# MIXR_Power_-_Connectors.net
KiCad netlist of a schematic drawn in Altium Designer
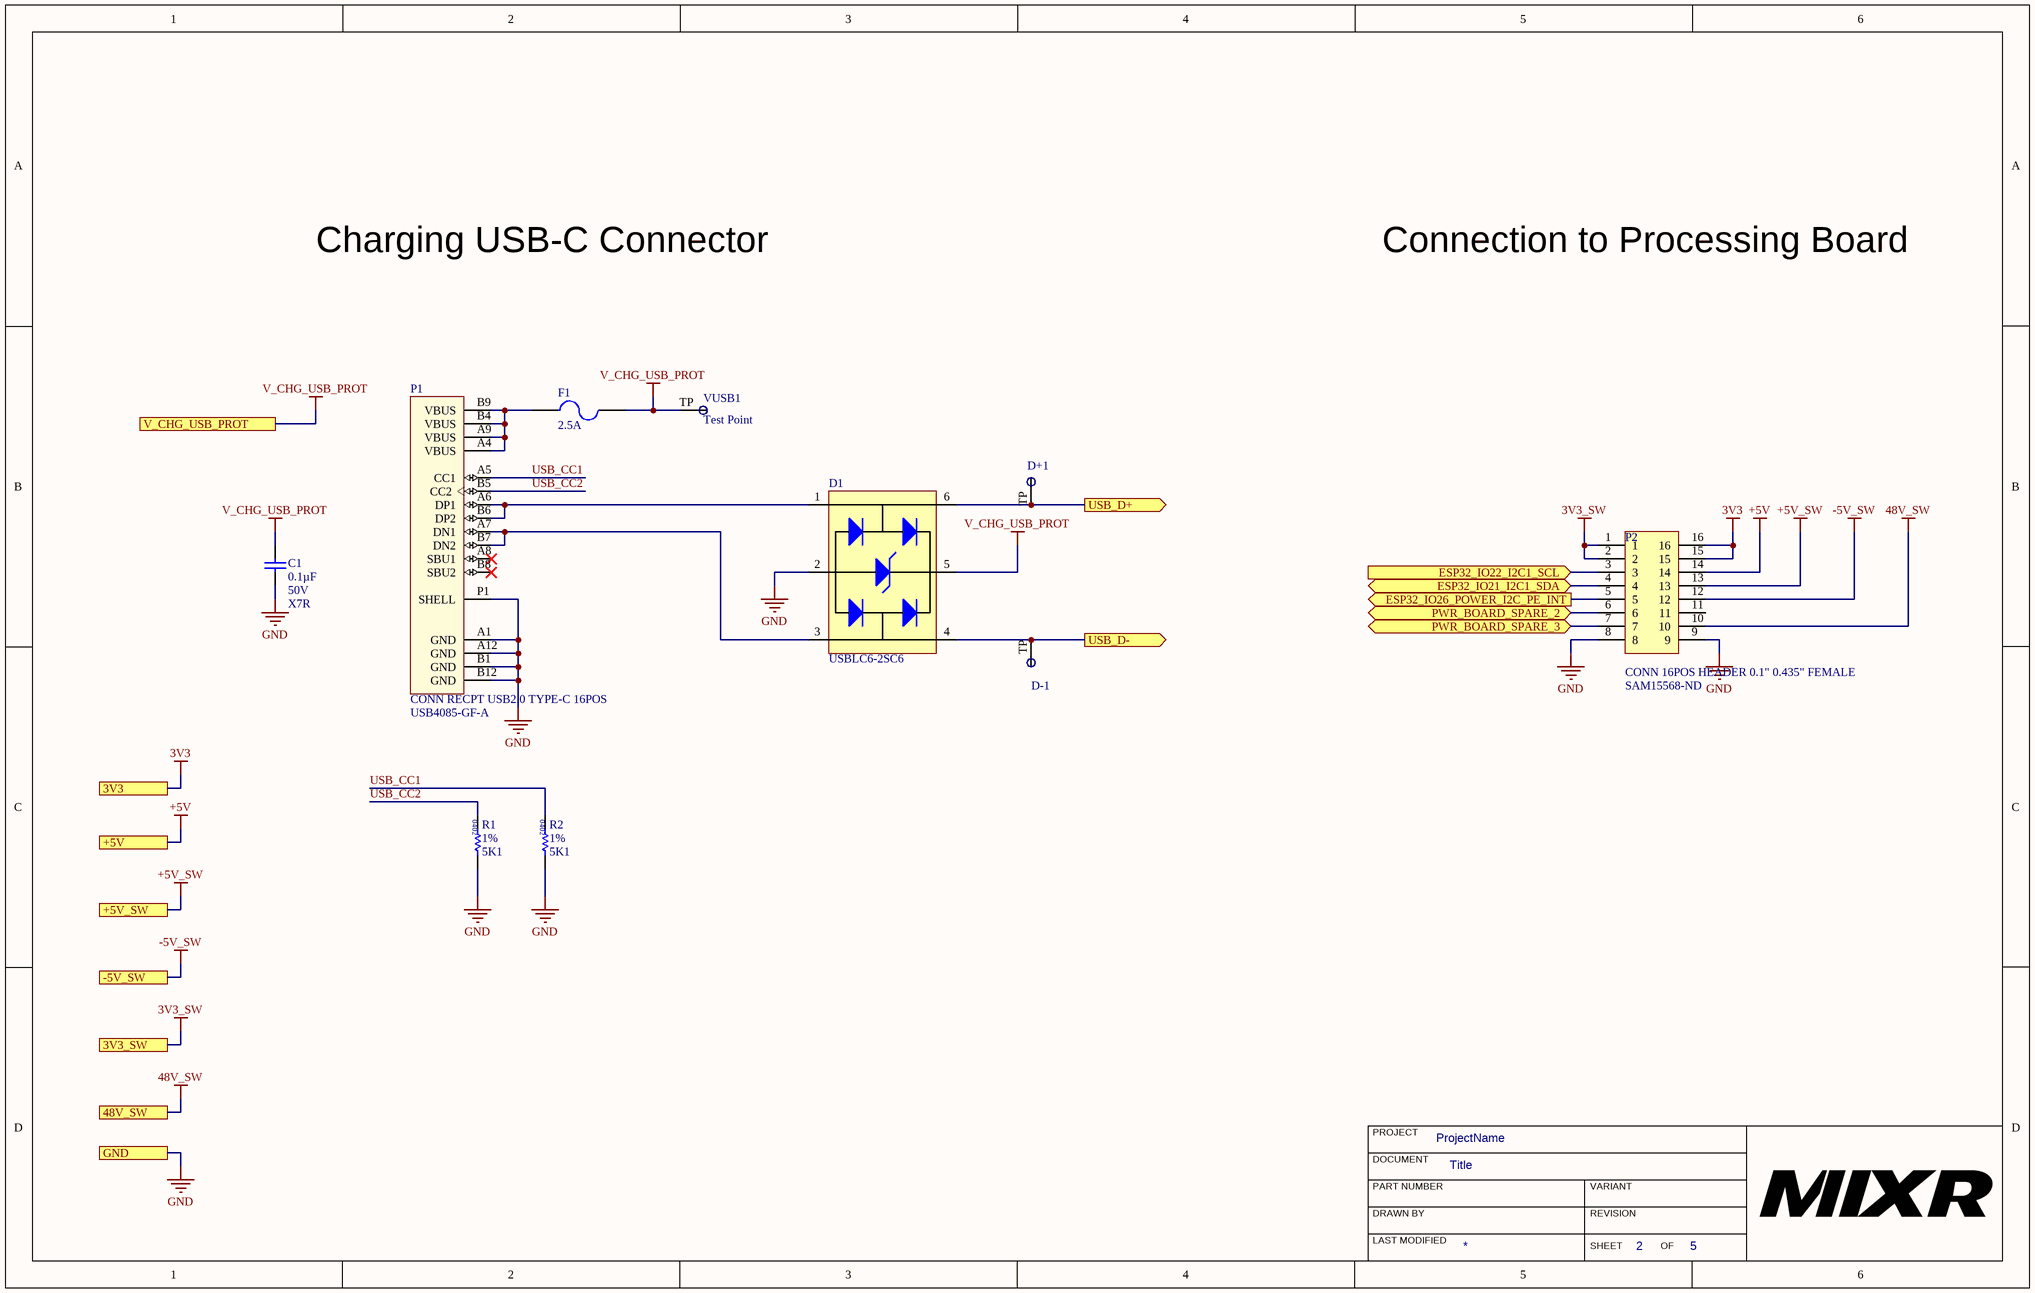
[diagram p0: MIXR Power - Connectors.SchDoc]

(export (version "E")
  (design (tool "Eeschema 10.0.6"))
  (components
    (comp (ref "C1")
      (value "CAP CER 0.1UF 50V 10% X7R 0603")
      (footprint "CAP, 0603")
      (description "0.10µF ±10% 50V Ceramic Capacitor X7R 0603 (1608 Metric)")
      (fields
        (field (name "TOLERANCE") "±10%")
        (field (name "CAPACITANCE") "0.1µF")
        (field (name "VOLTAGE") "50V")
        (field (name "TEMPERATURE COEFFICIENT") "X7R")
      )
      (libsource (lib "Schematic Diagrams") (part "CAP CER 0.1UF 50V 10% X7R 0603"))
    )
    (comp (ref "D+1")
      (value "Test Point")
      (footprint "Test Point")
      (libsource (lib "Schematic Diagrams") (part "Test Point"))
    )
    (comp (ref "D-1")
      (value "Test Point")
      (footprint "Test Point")
      (libsource (lib "Schematic Diagrams") (part "Test Point"))
    )
    (comp (ref "D1")
      (value "DIODE TVS 5.25V 17V SOT23-6")
      (footprint "SOT23-6")
      (description "17V Clamp 5A (8/20µs) Ipp Tvs Diode Surface Mount SOT-23-6")
      (fields (field (name "MANUFACTURER PART NUMBER 1") "USBLC6-2SC6"))
      (libsource (lib "Schematic Diagrams") (part "DIODE TVS 5.25V 17V SOT23-6"))
    )
    (comp (ref "F1")
      (value "FUSE 2.5A 32VDC 1206")
      (footprint "FUSE LITTLEFUSE 0466 1206")
      (description "2.5A 32V AC 32V DC Fuse Board Mount (Cartridge Style Excluded) Surface Mount 1206 (3216 Metric)")
      (fields (field (name "CURRENT RATING") "2.5A"))
      (libsource (lib "Schematic Diagrams") (part "FUSE 2.5A 32VDC 1206"))
    )
    (comp (ref "P1")
      (value "CONN RECPT USB2.0 TYPE-C 16POS")
      (footprint "CONN RECPT USB2.0 TYPE C 16-POS")
      (description "USB - C USB 2.0 Receptacle Connector 16 Position Through Hole, Right Angle")
      (fields
        (field (name "MANUFACTURER") "Global Connector Technology")
        (field (name "MANUFACTURER PART NUMBER") "USB4085-GF-A")
      )
      (libsource (lib "Schematic Diagrams") (part "CONN RECPT USB2.0 TYPE-C 16POS"))
    )
    (comp (ref "P2")
      (value "CONN 16POS HEADER 0.1\" 0.435\" FEMALE")
      (footprint "CONN, 16POS 0.100\" 0.435\" FEMALE")
      (description "Conn Elevated Socket SKT 16 POS 2.54mm Solder ST Thru-Hole Tube")
      (fields
        (field (name "MANUFACTURER") "Samtec")
        (field (name "MANUFACTURER PART NUMBER") "ESQ-108-12-T-D")
        (field (name "SUPPLIER PART NUMBER 1") "SAM15568-ND")
      )
      (libsource (lib "Schematic Diagrams") (part "CONN 16POS HEADER 0.1{dblquote} 0.435{dblquote} FEMALE"))
    )
    (comp (ref "R1")
      (value "RES 5.1K OHM 1% 1/16W 0402")
      (footprint "RES 0402")
      (description "5.1 kOhms ±1% 0.063W, 1/16W Chip Resistor 0402 (1005 Metric) Automotive AEC-Q200 Thick Film")
      (fields
        (field (name "MANUFACTURER") "Stackpole Electronics")
        (field (name "MANUFACTURER PART NUMBER") "RMCF0402FT5K10")
        (field (name "TOLERANCE") "1%")
        (field (name "RESISTANCE") "5K1")
      )
      (libsource (lib "Schematic Diagrams") (part "RES 5.1K OHM 1% 1/16W 0402"))
    )
    (comp (ref "R2")
      (value "RES 5.1K OHM 1% 1/16W 0402")
      (footprint "RES 0402")
      (description "5.1 kOhms ±1% 0.063W, 1/16W Chip Resistor 0402 (1005 Metric) Automotive AEC-Q200 Thick Film")
      (fields
        (field (name "MANUFACTURER") "Stackpole Electronics")
        (field (name "MANUFACTURER PART NUMBER") "RMCF0402FT5K10")
        (field (name "TOLERANCE") "1%")
        (field (name "RESISTANCE") "5K1")
      )
      (libsource (lib "Schematic Diagrams") (part "RES 5.1K OHM 1% 1/16W 0402"))
    )
    (comp (ref "VUSB1")
      (value "Test Point")
      (footprint "Test Point")
      (libsource (lib "Schematic Diagrams") (part "Test Point"))
    )
  )
  (nets
    (net (code "1") (name "+5V") (class "Default")
      (node (ref "P2") (pin "14") (pinfunction "14_14") (pintype "passive"))
    )
    (net (code "2") (name "+5V_SW") (class "Default")
      (node (ref "P2") (pin "13") (pinfunction "13_13") (pintype "passive"))
    )
    (net (code "3") (name "-5V_SW") (class "Default")
      (node (ref "P2") (pin "12") (pinfunction "12_12") (pintype "passive"))
    )
    (net (code "4") (name "/ESP32_IO21_I2C1_SDA") (class "Default")
      (node (ref "P2") (pin "4") (pinfunction "4_4") (pintype "passive"))
    )
    (net (code "5") (name "/ESP32_IO22_I2C1_SCL") (class "Default")
      (node (ref "P2") (pin "3") (pinfunction "3_3") (pintype "passive"))
    )
    (net (code "6") (name "/ESP32_IO26_POWER_I2C_PE_INT") (class "Default")
      (node (ref "P2") (pin "5") (pinfunction "5_5") (pintype "passive"))
    )
    (net (code "7") (name "/PWR_BOARD_SPARE_2") (class "Default")
      (node (ref "P2") (pin "6") (pinfunction "6_6") (pintype "passive"))
    )
    (net (code "8") (name "/PWR_BOARD_SPARE_3") (class "Default")
      (node (ref "P2") (pin "7") (pinfunction "7_7") (pintype "passive"))
    )
    (net (code "9") (name "/USB_CC1") (class "Default")
      (node (ref "P1") (pin "A5") (pinfunction "CC1_A5") (pintype "bidirectional"))
      (node (ref "R2") (pin "1") (pinfunction "1_1") (pintype "passive"))
    )
    (net (code "10") (name "/USB_CC2") (class "Default")
      (node (ref "P1") (pin "B5") (pinfunction "CC2_B5") (pintype "bidirectional"))
      (node (ref "R1") (pin "1") (pinfunction "1_1") (pintype "passive"))
    )
    (net (code "11") (name "/USB_D+") (class "Default")
      (node (ref "D+1") (pin "TP") (pinfunction "1_TP") (pintype "passive"))
      (node (ref "D1") (pin "6") (pinfunction "Cathode3_6") (pintype "passive"))
    )
    (net (code "12") (name "/USB_D-") (class "Default")
      (node (ref "D-1") (pin "TP") (pinfunction "1_TP") (pintype "passive"))
      (node (ref "D1") (pin "4") (pinfunction "Cathode2_4") (pintype "passive"))
    )
    (net (code "13") (name "3V3") (class "Default")
      (node (ref "P2") (pin "15") (pinfunction "15_15") (pintype "passive"))
      (node (ref "P2") (pin "16") (pinfunction "16_16") (pintype "passive"))
    )
    (net (code "14") (name "3V3_SW") (class "Default")
      (node (ref "P2") (pin "1") (pinfunction "1_1") (pintype "passive"))
      (node (ref "P2") (pin "2") (pinfunction "2_2") (pintype "passive"))
    )
    (net (code "15") (name "48V_SW") (class "Default")
      (node (ref "P2") (pin "10") (pinfunction "10_10") (pintype "passive"))
    )
    (net (code "16") (name "GND") (class "Default")
      (node (ref "C1") (pin "2") (pinfunction "2_2") (pintype "passive"))
      (node (ref "D1") (pin "2") (pinfunction "Cathode2_2") (pintype "passive"))
      (node (ref "P1") (pin "A1") (pinfunction "GND_A1") (pintype "power_in"))
      (node (ref "P1") (pin "A12") (pinfunction "GND_A12") (pintype "power_in"))
      (node (ref "P1") (pin "B1") (pinfunction "GND_B1") (pintype "passive"))
      (node (ref "P1") (pin "B12") (pinfunction "GND_B12") (pintype "power_in"))
      (node (ref "P1") (pin "P1") (pinfunction "SHELL_P1") (pintype "passive"))
      (node (ref "P2") (pin "8") (pinfunction "8_8") (pintype "passive"))
      (node (ref "P2") (pin "9") (pinfunction "9_9") (pintype "passive"))
      (node (ref "R1") (pin "2") (pinfunction "2_2") (pintype "passive"))
      (node (ref "R2") (pin "2") (pinfunction "2_2") (pintype "passive"))
    )
    (net (code "17") (name "Net-(D1-Cathode1)") (class "Default")
      (node (ref "D1") (pin "3") (pinfunction "Cathode1_3") (pintype "passive"))
      (node (ref "P1") (pin "A7") (pinfunction "DN1_A7") (pintype "bidirectional"))
      (node (ref "P1") (pin "B7") (pinfunction "DN2_B7") (pintype "bidirectional"))
    )
    (net (code "18") (name "Net-(F1-Pad1)") (class "Default")
      (node (ref "F1") (pin "1") (pinfunction "1_1") (pintype "passive"))
      (node (ref "P1") (pin "A4") (pinfunction "VBUS_A4") (pintype "power_in"))
      (node (ref "P1") (pin "A9") (pinfunction "VBUS_A9") (pintype "power_in"))
      (node (ref "P1") (pin "B4") (pinfunction "VBUS_B4") (pintype "power_in"))
      (node (ref "P1") (pin "B9") (pinfunction "VBUS_B9") (pintype "power_in"))
    )
    (net (code "19") (name "Net-(P1-DP1)") (class "Default")
      (node (ref "D1") (pin "1") (pinfunction "Cathode3_1") (pintype "passive"))
      (node (ref "P1") (pin "A6") (pinfunction "DP1_A6") (pintype "bidirectional"))
      (node (ref "P1") (pin "B6") (pinfunction "DP2_B6") (pintype "bidirectional"))
    )
    (net (code "20") (name "V_CHG_USB_PROT") (class "Default")
      (node (ref "C1") (pin "1") (pinfunction "1_1") (pintype "passive"))
      (node (ref "D1") (pin "5") (pinfunction "Cathode4_5") (pintype "passive"))
      (node (ref "F1") (pin "2") (pinfunction "2_2") (pintype "passive"))
      (node (ref "VUSB1") (pin "TP") (pinfunction "1_TP") (pintype "passive"))
    )
    (net (code "21") (name "unconnected-(P1-SBU1-PadA8)") (class "Default")
      (node (ref "P1") (pin "A8") (pinfunction "SBU1_A8") (pintype "bidirectional+no_connect"))
    )
    (net (code "22") (name "unconnected-(P1-SBU2-PadB8)") (class "Default")
      (node (ref "P1") (pin "B8") (pinfunction "SBU2_B8") (pintype "bidirectional+no_connect"))
    )
    (net (code "23") (name "unconnected-(P2-Pad11)") (class "Default")
      (node (ref "P2") (pin "11") (pinfunction "11_11") (pintype "passive"))
    )
  )
)
